# Final.net
KiCad netlist of a schematic drawn in EAGLE
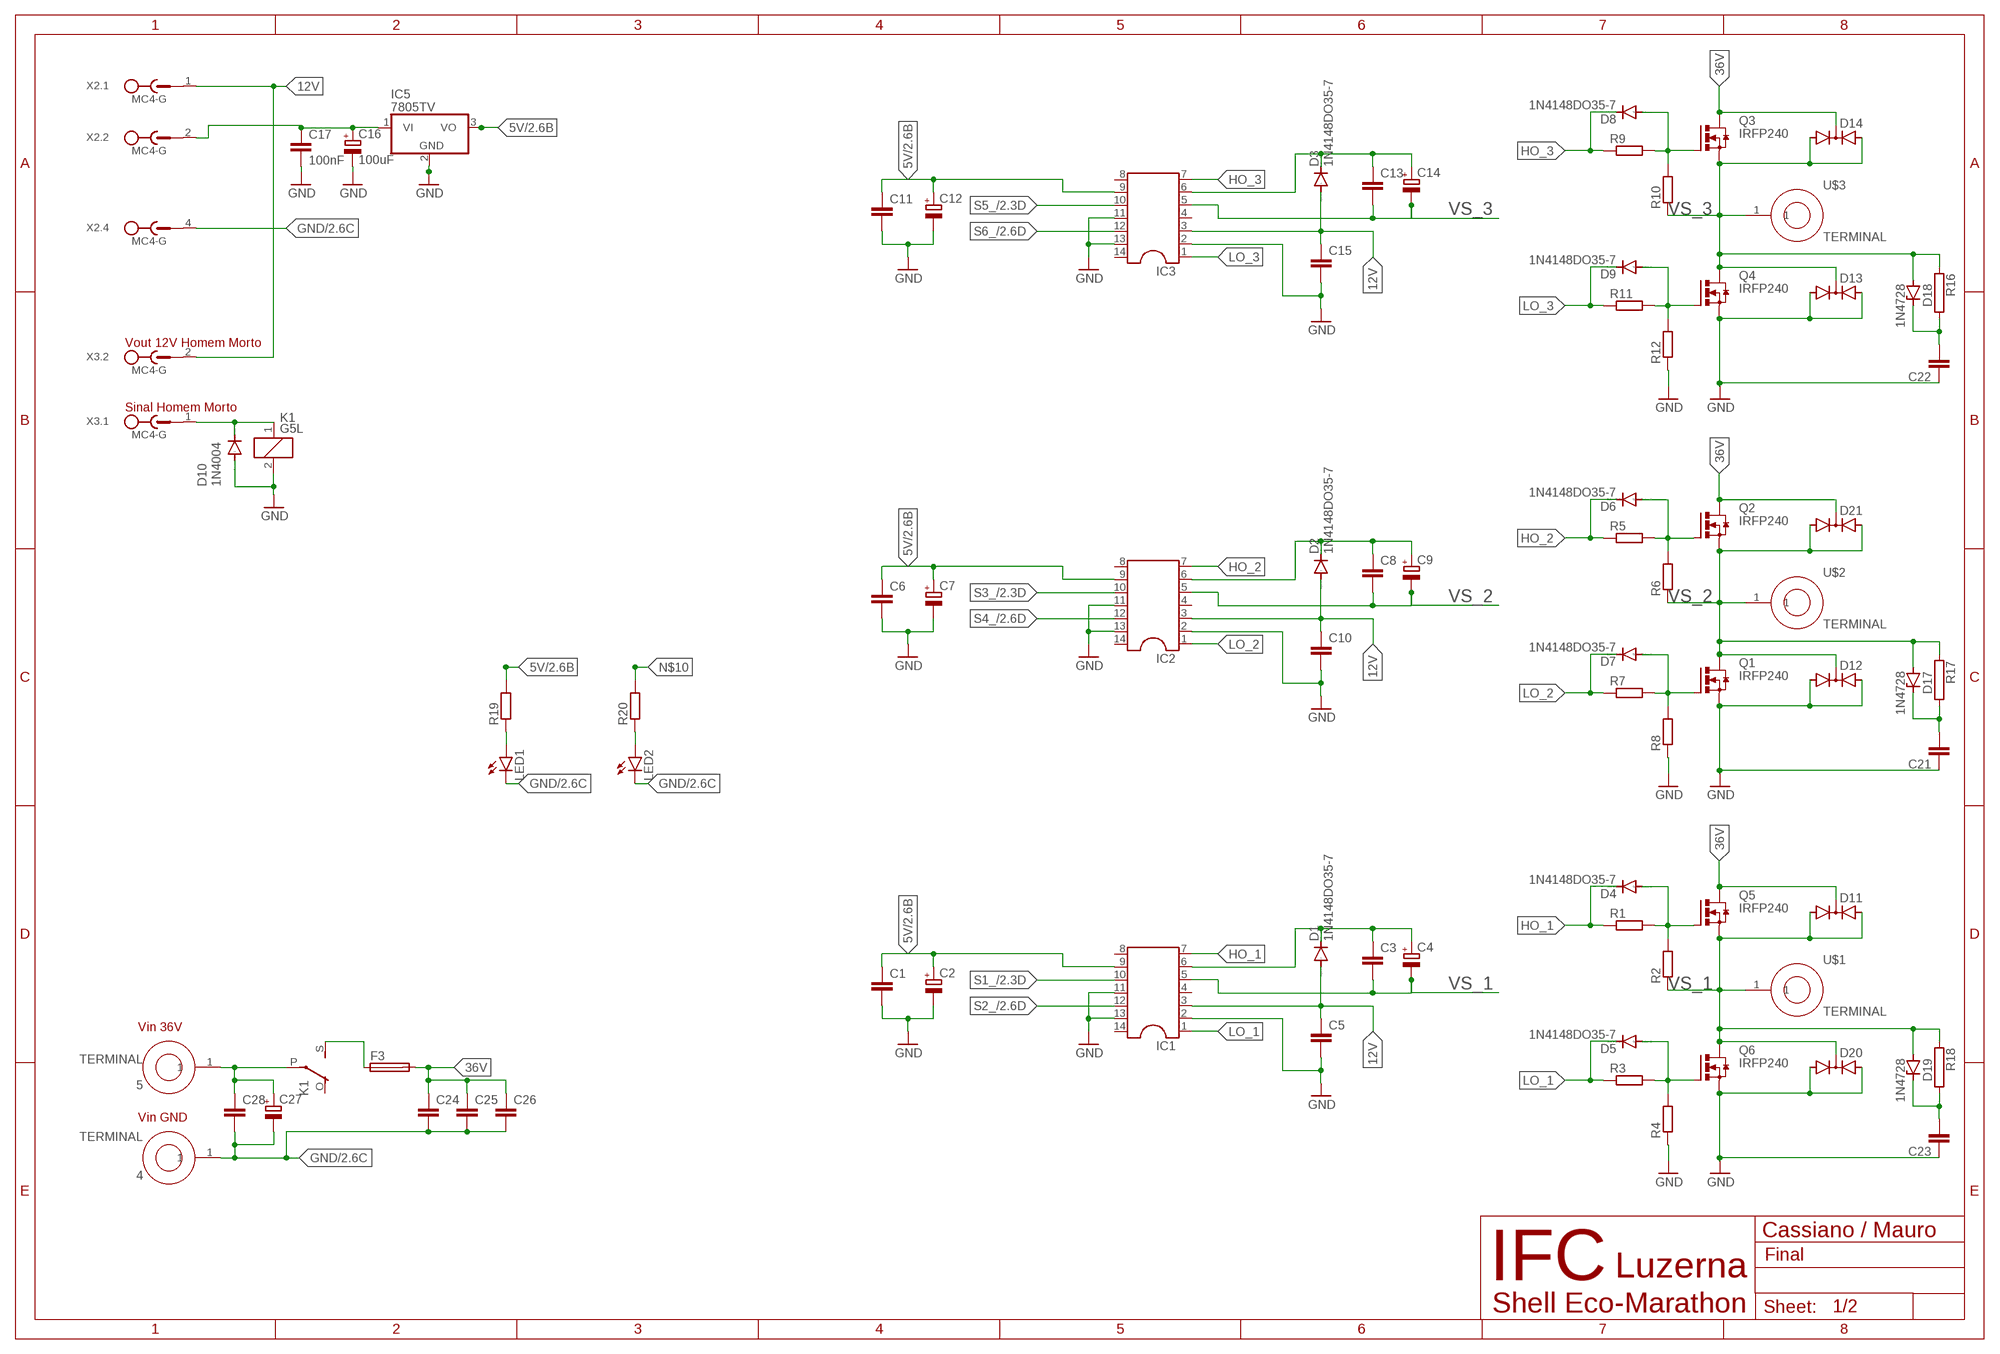
[diagram p0: schematic, sheet 1]
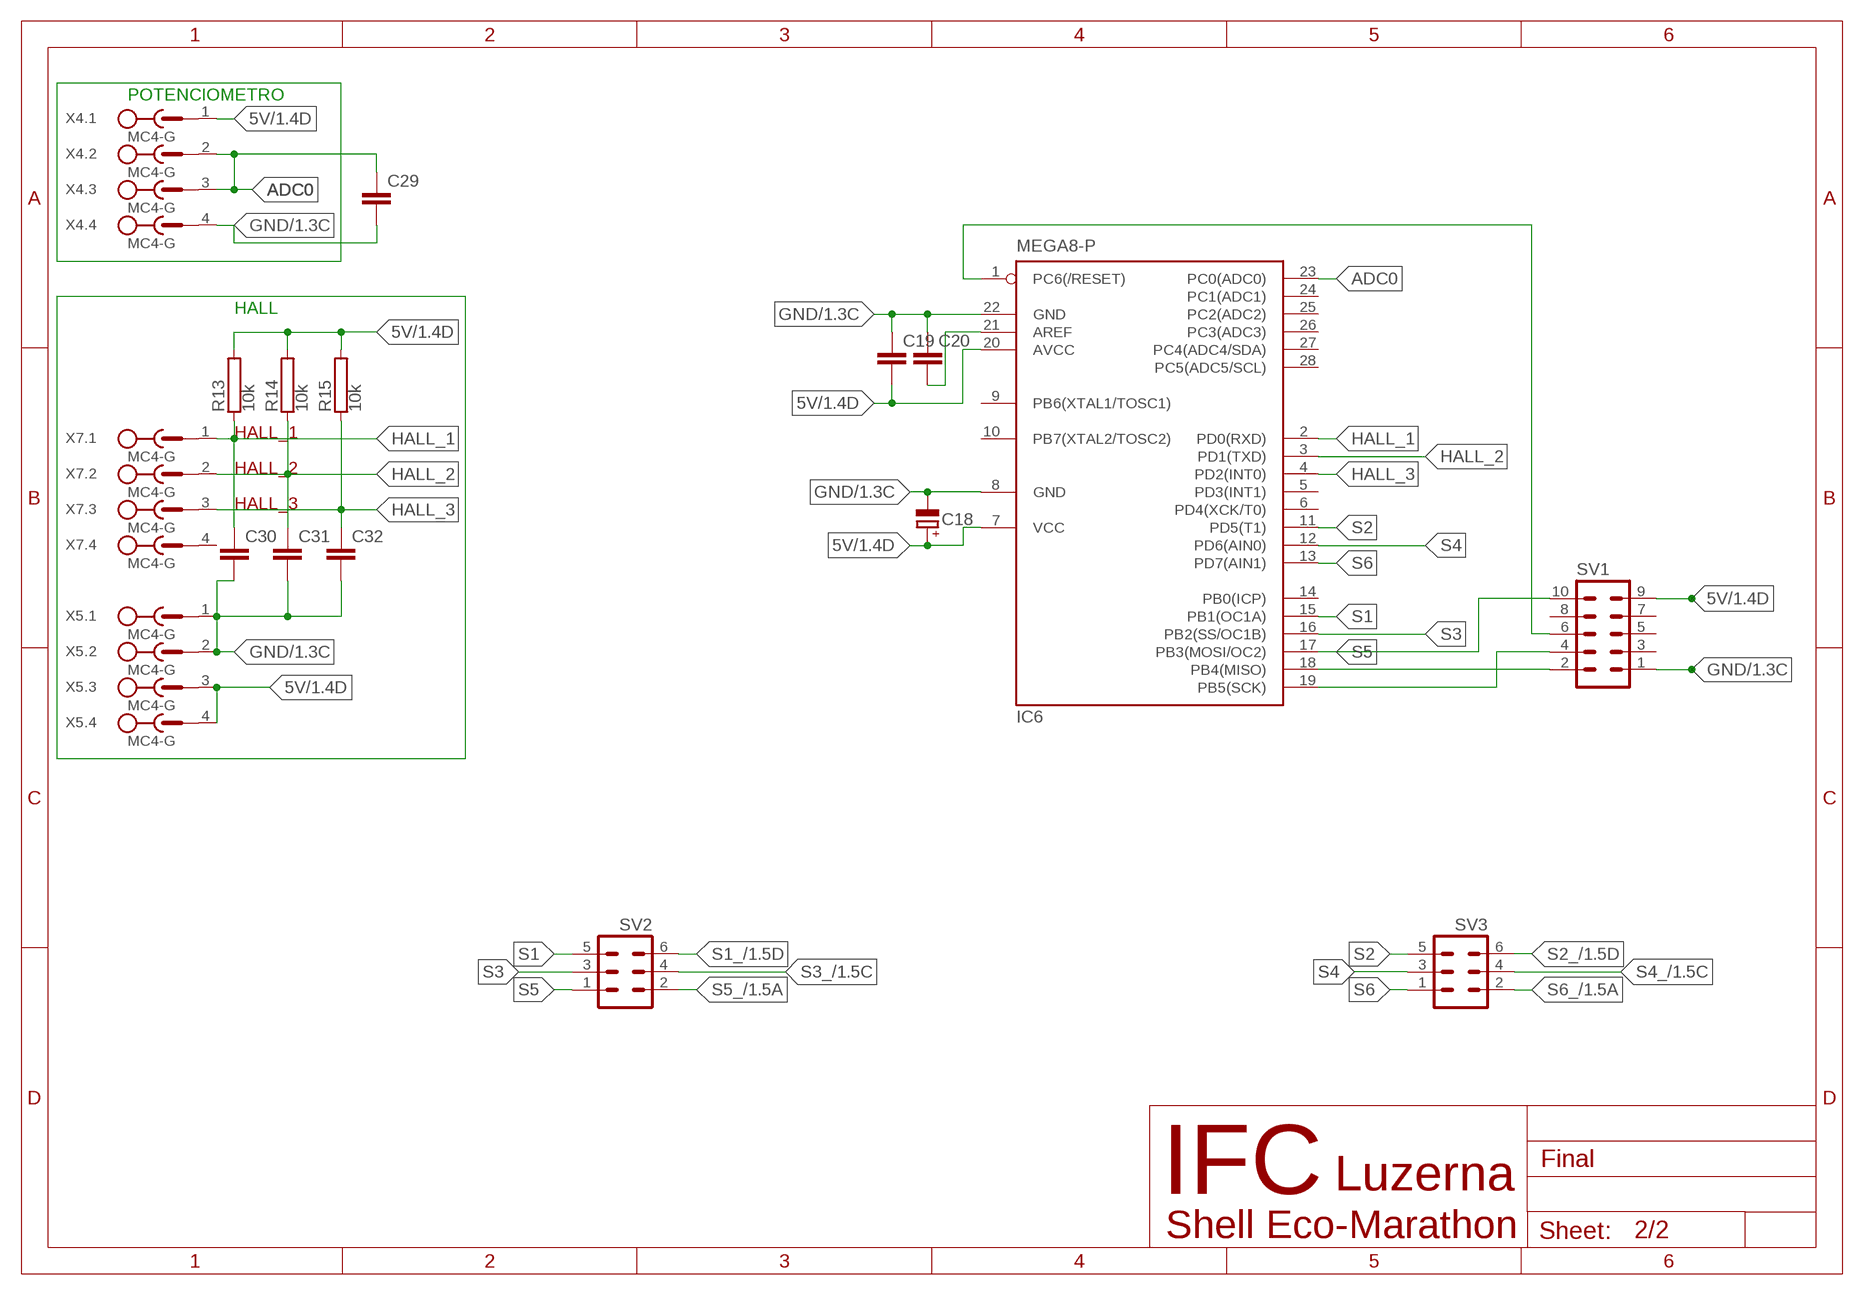
[diagram p1: schematic, sheet 2]

(export (version "E")
  (design (tool "Eeschema 10.0.6"))
  (components
    (comp (ref "4")
      (value "TERMINAL")
      (footprint "eagle-import:TERMINAL")
      (libsource (lib "eagle-import") (part "TERMINAL"))
    )
    (comp (ref "5")
      (value "TERMINAL")
      (footprint "eagle-import:TERMINAL")
      (libsource (lib "eagle-import") (part "TERMINAL"))
    )
    (comp (ref "C1")
      (value "C-EU050-045X075")
      (footprint "eagle-import:C050-045X075")
      (libsource (lib "eagle-import") (part "C-EU050-045X075"))
    )
    (comp (ref "C2")
      (value "CPOL-EUE2.5-7")
      (footprint "eagle-import:E2,5-7")
      (libsource (lib "eagle-import") (part "CPOL-EUE2.5-7"))
    )
    (comp (ref "C3")
      (value "C-EU050-025X075")
      (footprint "eagle-import:C050-025X075")
      (libsource (lib "eagle-import") (part "C-EU050-025X075"))
    )
    (comp (ref "C4")
      (value "CPOL-EUE2.5-7")
      (footprint "eagle-import:E2,5-7")
      (libsource (lib "eagle-import") (part "CPOL-EUE2.5-7"))
    )
    (comp (ref "C5")
      (value "C-EU050-025X075")
      (footprint "eagle-import:C050-025X075")
      (libsource (lib "eagle-import") (part "C-EU050-025X075"))
    )
    (comp (ref "C6")
      (value "C-EU050-045X075")
      (footprint "eagle-import:C050-045X075")
      (libsource (lib "eagle-import") (part "C-EU050-045X075"))
    )
    (comp (ref "C7")
      (value "CPOL-EUE2.5-7")
      (footprint "eagle-import:E2,5-7")
      (libsource (lib "eagle-import") (part "CPOL-EUE2.5-7"))
    )
    (comp (ref "C8")
      (value "C-EU050-025X075")
      (footprint "eagle-import:C050-025X075")
      (libsource (lib "eagle-import") (part "C-EU050-025X075"))
    )
    (comp (ref "C9")
      (value "CPOL-EUE2.5-7")
      (footprint "eagle-import:E2,5-7")
      (libsource (lib "eagle-import") (part "CPOL-EUE2.5-7"))
    )
    (comp (ref "C10")
      (value "C-EU050-025X075")
      (footprint "eagle-import:C050-025X075")
      (libsource (lib "eagle-import") (part "C-EU050-025X075"))
    )
    (comp (ref "C11")
      (value "C-EU050-045X075")
      (footprint "eagle-import:C050-045X075")
      (libsource (lib "eagle-import") (part "C-EU050-045X075"))
    )
    (comp (ref "C12")
      (value "CPOL-EUE2.5-7")
      (footprint "eagle-import:E2,5-7")
      (libsource (lib "eagle-import") (part "CPOL-EUE2.5-7"))
    )
    (comp (ref "C13")
      (value "C-EU050-025X075")
      (footprint "eagle-import:C050-025X075")
      (libsource (lib "eagle-import") (part "C-EU050-025X075"))
    )
    (comp (ref "C14")
      (value "CPOL-EUE2.5-7")
      (footprint "eagle-import:E2,5-7")
      (libsource (lib "eagle-import") (part "CPOL-EUE2.5-7"))
    )
    (comp (ref "C15")
      (value "C-EU050-025X075")
      (footprint "eagle-import:C050-025X075")
      (libsource (lib "eagle-import") (part "C-EU050-025X075"))
    )
    (comp (ref "C16")
      (value "100uF")
      (footprint "eagle-import:E2,5-7")
      (libsource (lib "eagle-import") (part "CPOL-EUE2.5-7"))
    )
    (comp (ref "C17")
      (value "100nF")
      (footprint "eagle-import:C050-045X075")
      (libsource (lib "eagle-import") (part "C-EU050-045X075"))
    )
    (comp (ref "C21")
      (value "C-EU150-054X183")
      (footprint "eagle-import:C150-054X183")
      (libsource (lib "eagle-import") (part "C-EU150-054X183"))
    )
    (comp (ref "C22")
      (value "C-EU150-054X183")
      (footprint "eagle-import:C150-054X183")
      (libsource (lib "eagle-import") (part "C-EU150-054X183"))
    )
    (comp (ref "C23")
      (value "C-EU150-054X183")
      (footprint "eagle-import:C150-054X183")
      (libsource (lib "eagle-import") (part "C-EU150-054X183"))
    )
    (comp (ref "C24")
      (value "C-EU275-093X316")
      (footprint "eagle-import:C275-093X316")
      (libsource (lib "eagle-import") (part "C-EU275-093X316"))
    )
    (comp (ref "C25")
      (value "C-EU275-093X316")
      (footprint "eagle-import:C275-093X316")
      (libsource (lib "eagle-import") (part "C-EU275-093X316"))
    )
    (comp (ref "C26")
      (value "C-EU275-093X316")
      (footprint "eagle-import:C275-093X316")
      (libsource (lib "eagle-import") (part "C-EU275-093X316"))
    )
    (comp (ref "C27")
      (value "CPOL-EUE10-22.5")
      (footprint "eagle-import:EB22,5D")
      (libsource (lib "eagle-import") (part "CPOL-EUE10-22.5"))
    )
    (comp (ref "C28")
      (value "C-EU275-093X316")
      (footprint "eagle-import:C275-093X316")
      (libsource (lib "eagle-import") (part "C-EU275-093X316"))
    )
    (comp (ref "D1")
      (value "1N4148DO35-7")
      (footprint "eagle-import:DO35-7")
      (libsource (lib "eagle-import") (part "1N4148DO35-7"))
    )
    (comp (ref "D2")
      (value "1N4148DO35-7")
      (footprint "eagle-import:DO35-7")
      (libsource (lib "eagle-import") (part "1N4148DO35-7"))
    )
    (comp (ref "D3")
      (value "1N4148DO35-7")
      (footprint "eagle-import:DO35-7")
      (libsource (lib "eagle-import") (part "1N4148DO35-7"))
    )
    (comp (ref "D4")
      (value "1N4148DO35-7")
      (footprint "eagle-import:DO35-7")
      (libsource (lib "eagle-import") (part "1N4148DO35-7"))
    )
    (comp (ref "D5")
      (value "1N4148DO35-7")
      (footprint "eagle-import:DO35-7")
      (libsource (lib "eagle-import") (part "1N4148DO35-7"))
    )
    (comp (ref "D6")
      (value "1N4148DO35-7")
      (footprint "eagle-import:DO35-7")
      (libsource (lib "eagle-import") (part "1N4148DO35-7"))
    )
    (comp (ref "D7")
      (value "1N4148DO35-7")
      (footprint "eagle-import:DO35-7")
      (libsource (lib "eagle-import") (part "1N4148DO35-7"))
    )
    (comp (ref "D8")
      (value "1N4148DO35-7")
      (footprint "eagle-import:DO35-7")
      (libsource (lib "eagle-import") (part "1N4148DO35-7"))
    )
    (comp (ref "D9")
      (value "1N4148DO35-7")
      (footprint "eagle-import:DO35-7")
      (libsource (lib "eagle-import") (part "1N4148DO35-7"))
    )
    (comp (ref "D10")
      (value "1N4004")
      (footprint "eagle-import:DO41-10")
      (libsource (lib "eagle-import") (part "1N4004"))
    )
    (comp (ref "D11")
      (value "DIODE-2AC|CATO220V")
      (footprint "eagle-import:TO220ABS")
      (libsource (lib "eagle-import") (part "DIODE-2AC|CATO220V"))
    )
    (comp (ref "D12")
      (value "DIODE-2AC|CATO220V")
      (footprint "eagle-import:TO220ABS")
      (libsource (lib "eagle-import") (part "DIODE-2AC|CATO220V"))
    )
    (comp (ref "D13")
      (value "DIODE-2AC|CATO220V")
      (footprint "eagle-import:TO220ABS")
      (libsource (lib "eagle-import") (part "DIODE-2AC|CATO220V"))
    )
    (comp (ref "D14")
      (value "DIODE-2AC|CATO220V")
      (footprint "eagle-import:TO220ABS")
      (libsource (lib "eagle-import") (part "DIODE-2AC|CATO220V"))
    )
    (comp (ref "D17")
      (value "1N4728")
      (footprint "eagle-import:DO41Z10")
      (libsource (lib "eagle-import") (part "1N4728"))
    )
    (comp (ref "D18")
      (value "1N4728")
      (footprint "eagle-import:DO41Z10")
      (libsource (lib "eagle-import") (part "1N4728"))
    )
    (comp (ref "D19")
      (value "1N4728")
      (footprint "eagle-import:DO41Z10")
      (libsource (lib "eagle-import") (part "1N4728"))
    )
    (comp (ref "D20")
      (value "DIODE-2AC|CATO220V")
      (footprint "eagle-import:TO220ABS")
      (libsource (lib "eagle-import") (part "DIODE-2AC|CATO220V"))
    )
    (comp (ref "D21")
      (value "DIODE-2AC|CATO220V")
      (footprint "eagle-import:TO220ABS")
      (libsource (lib "eagle-import") (part "DIODE-2AC|CATO220V"))
    )
    (comp (ref "F3")
      (value "SH22,5A")
      (footprint "eagle-import:SH22,5A")
      (fields (field (name "MPN") "0031.7701.11"))
      (libsource (lib "eagle-import") (part "SH22,5A"))
    )
    (comp (ref "IC1")
      (value "DIL14")
      (footprint "eagle-import:DIL14")
      (libsource (lib "eagle-import") (part "DIL14"))
    )
    (comp (ref "IC2")
      (value "DIL14")
      (footprint "eagle-import:DIL14")
      (libsource (lib "eagle-import") (part "DIL14"))
    )
    (comp (ref "IC3")
      (value "DIL14")
      (footprint "eagle-import:DIL14")
      (libsource (lib "eagle-import") (part "DIL14"))
    )
    (comp (ref "IC5")
      (value "7805TV")
      (footprint "eagle-import:TO220V")
      (libsource (lib "eagle-import") (part "78TV05"))
    )
    (comp (ref "K1")
      (value "G5L")
      (footprint "eagle-import:G5LE")
      (libsource (lib "eagle-import") (part "G5L"))
    )
    (comp (ref "LED1")
      (value "LED5MM")
      (footprint "eagle-import:LED5MM")
      (libsource (lib "eagle-import") (part "LED5MM"))
    )
    (comp (ref "LED2")
      (value "LED5MM")
      (footprint "eagle-import:LED5MM")
      (libsource (lib "eagle-import") (part "LED5MM"))
    )
    (comp (ref "Q1")
      (value "IRFP240")
      (footprint "eagle-import:TO247BV")
      (libsource (lib "eagle-import") (part "IRFP240"))
    )
    (comp (ref "Q2")
      (value "IRFP240")
      (footprint "eagle-import:TO247BV")
      (libsource (lib "eagle-import") (part "IRFP240"))
    )
    (comp (ref "Q3")
      (value "IRFP240")
      (footprint "eagle-import:TO247BV")
      (libsource (lib "eagle-import") (part "IRFP240"))
    )
    (comp (ref "Q4")
      (value "IRFP240")
      (footprint "eagle-import:TO247BV")
      (libsource (lib "eagle-import") (part "IRFP240"))
    )
    (comp (ref "Q5")
      (value "IRFP240")
      (footprint "eagle-import:TO247BV")
      (libsource (lib "eagle-import") (part "IRFP240"))
    )
    (comp (ref "Q6")
      (value "IRFP240")
      (footprint "eagle-import:TO247BV")
      (libsource (lib "eagle-import") (part "IRFP240"))
    )
    (comp (ref "R1")
      (value "R-EU_0204/7")
      (footprint "eagle-import:0204_7")
      (libsource (lib "eagle-import") (part "R-EU_0204/7"))
    )
    (comp (ref "R2")
      (value "R-EU_0204/7")
      (footprint "eagle-import:0204_7")
      (libsource (lib "eagle-import") (part "R-EU_0204/7"))
    )
    (comp (ref "R3")
      (value "R-EU_0204/7")
      (footprint "eagle-import:0204_7")
      (libsource (lib "eagle-import") (part "R-EU_0204/7"))
    )
    (comp (ref "R4")
      (value "R-EU_0204/7")
      (footprint "eagle-import:0204_7")
      (libsource (lib "eagle-import") (part "R-EU_0204/7"))
    )
    (comp (ref "R5")
      (value "R-EU_0204/7")
      (footprint "eagle-import:0204_7")
      (libsource (lib "eagle-import") (part "R-EU_0204/7"))
    )
    (comp (ref "R6")
      (value "R-EU_0204/7")
      (footprint "eagle-import:0204_7")
      (libsource (lib "eagle-import") (part "R-EU_0204/7"))
    )
    (comp (ref "R7")
      (value "R-EU_0204/7")
      (footprint "eagle-import:0204_7")
      (libsource (lib "eagle-import") (part "R-EU_0204/7"))
    )
    (comp (ref "R8")
      (value "R-EU_0204/7")
      (footprint "eagle-import:0204_7")
      (libsource (lib "eagle-import") (part "R-EU_0204/7"))
    )
    (comp (ref "R9")
      (value "R-EU_0204/7")
      (footprint "eagle-import:0204_7")
      (libsource (lib "eagle-import") (part "R-EU_0204/7"))
    )
    (comp (ref "R10")
      (value "R-EU_0204/7")
      (footprint "eagle-import:0204_7")
      (libsource (lib "eagle-import") (part "R-EU_0204/7"))
    )
    (comp (ref "R11")
      (value "R-EU_0204/7")
      (footprint "eagle-import:0204_7")
      (libsource (lib "eagle-import") (part "R-EU_0204/7"))
    )
    (comp (ref "R12")
      (value "R-EU_0204/7")
      (footprint "eagle-import:0204_7")
      (libsource (lib "eagle-import") (part "R-EU_0204/7"))
    )
    (comp (ref "R16")
      (value "RCA4150")
      (footprint "eagle-import:CA4150")
      (libsource (lib "eagle-import") (part "RCA4150"))
    )
    (comp (ref "R17")
      (value "RCA4150")
      (footprint "eagle-import:CA4150")
      (libsource (lib "eagle-import") (part "RCA4150"))
    )
    (comp (ref "R18")
      (value "RCA4150")
      (footprint "eagle-import:CA4150")
      (libsource (lib "eagle-import") (part "RCA4150"))
    )
    (comp (ref "R19")
      (value "R-EU_0204/7")
      (footprint "eagle-import:0204_7")
      (libsource (lib "eagle-import") (part "R-EU_0204/7"))
    )
    (comp (ref "R20")
      (value "R-EU_0204/7")
      (footprint "eagle-import:0204_7")
      (libsource (lib "eagle-import") (part "R-EU_0204/7"))
    )
    (comp (ref "U$1")
      (value "TERMINAL")
      (footprint "eagle-import:TERMINAL")
      (libsource (lib "eagle-import") (part "TERMINAL"))
    )
    (comp (ref "U$2")
      (value "TERMINAL")
      (footprint "eagle-import:TERMINAL")
      (libsource (lib "eagle-import") (part "TERMINAL"))
    )
    (comp (ref "U$3")
      (value "TERMINAL")
      (footprint "eagle-import:TERMINAL")
      (libsource (lib "eagle-import") (part "TERMINAL"))
    )
    (comp (ref "X2")
      (value "MC4-G")
      (footprint "eagle-import:MC4-G")
      (libsource (lib "eagle-import") (part "MC4-G"))
    )
    (comp (ref "X3")
      (value "MC4-G")
      (footprint "eagle-import:MC4-G")
      (libsource (lib "eagle-import") (part "MC4-G"))
    )
    (comp (ref "C18")
      (value "CPOL-EUE3.5-10")
      (footprint "eagle-import:E3,5-10")
      (libsource (lib "eagle-import") (part "CPOL-EUE3.5-10"))
    )
    (comp (ref "C19")
      (value "C-EU075-032X103")
      (footprint "eagle-import:C075-032X103")
      (libsource (lib "eagle-import") (part "C-EU075-032X103"))
    )
    (comp (ref "C20")
      (value "C-EU075-032X103")
      (footprint "eagle-import:C075-032X103")
      (libsource (lib "eagle-import") (part "C-EU075-032X103"))
    )
    (comp (ref "C29")
      (value "C-EU075-032X103")
      (footprint "eagle-import:C075-032X103")
      (libsource (lib "eagle-import") (part "C-EU075-032X103"))
    )
    (comp (ref "C30")
      (value "C-EU075-032X103")
      (footprint "eagle-import:C075-032X103")
      (libsource (lib "eagle-import") (part "C-EU075-032X103"))
    )
    (comp (ref "C31")
      (value "C-EU075-032X103")
      (footprint "eagle-import:C075-032X103")
      (libsource (lib "eagle-import") (part "C-EU075-032X103"))
    )
    (comp (ref "C32")
      (value "C-EU075-032X103")
      (footprint "eagle-import:C075-032X103")
      (libsource (lib "eagle-import") (part "C-EU075-032X103"))
    )
    (comp (ref "IC6")
      (value "MEGA8-P")
      (footprint "eagle-import:DIL28-3")
      (libsource (lib "eagle-import") (part "MEGA8-P"))
    )
    (comp (ref "R13")
      (value "10k")
      (footprint "eagle-import:RS1_4")
      (fields (field (name "MF") "OHMITE") (field (name "MPN") "RRS1K0"))
      (libsource (lib "eagle-import") (part "RRS1/4"))
    )
    (comp (ref "R14")
      (value "10k")
      (footprint "eagle-import:RS1_4")
      (fields (field (name "MF") "OHMITE") (field (name "MPN") "RRS1K0"))
      (libsource (lib "eagle-import") (part "RRS1/4"))
    )
    (comp (ref "R15")
      (value "10k")
      (footprint "eagle-import:RS1_4")
      (fields (field (name "MF") "OHMITE") (field (name "MPN") "RRS1K0"))
      (libsource (lib "eagle-import") (part "RRS1/4"))
    )
    (comp (ref "SV1")
      (value "MA05-2")
      (footprint "eagle-import:MA05-2")
      (libsource (lib "eagle-import") (part "MA05-2"))
    )
    (comp (ref "SV2")
      (value "MA03-2")
      (footprint "eagle-import:MA03-2")
      (libsource (lib "eagle-import") (part "MA03-2"))
    )
    (comp (ref "SV3")
      (value "MA03-2")
      (footprint "eagle-import:MA03-2")
      (libsource (lib "eagle-import") (part "MA03-2"))
    )
    (comp (ref "X4")
      (value "MC4-G")
      (footprint "eagle-import:MC4-G")
      (libsource (lib "eagle-import") (part "MC4-G"))
    )
    (comp (ref "X5")
      (value "MC4-G")
      (footprint "eagle-import:MC4-G")
      (libsource (lib "eagle-import") (part "MC4-G"))
    )
    (comp (ref "X7")
      (value "MC4-G")
      (footprint "eagle-import:MC4-G")
      (libsource (lib "eagle-import") (part "MC4-G"))
    )
  )
  (nets
    (net (code "1") (name "5V") (class "Default")
      (node (ref "C1") (pin "1") (pinfunction "1_1") (pintype "passive"))
      (node (ref "C11") (pin "1") (pinfunction "1_1") (pintype "passive"))
      (node (ref "C12") (pin "+") (pinfunction "+_+") (pintype "passive"))
      (node (ref "C18") (pin "+") (pinfunction "+_+") (pintype "passive"))
      (node (ref "C19") (pin "2") (pinfunction "2_2") (pintype "passive"))
      (node (ref "C2") (pin "+") (pinfunction "+_+") (pintype "passive"))
      (node (ref "C6") (pin "1") (pinfunction "1_1") (pintype "passive"))
      (node (ref "C7") (pin "+") (pinfunction "+_+") (pintype "passive"))
      (node (ref "IC1") (pin "9") (pinfunction "9_9") (pintype "passive"))
      (node (ref "IC2") (pin "9") (pinfunction "9_9") (pintype "passive"))
      (node (ref "IC3") (pin "9") (pinfunction "9_9") (pintype "passive"))
      (node (ref "IC5") (pin "3") (pinfunction "VO_3") (pintype "passive"))
      (node (ref "IC6") (pin "20") (pinfunction "AVCC_20") (pintype "power_in"))
      (node (ref "IC6") (pin "7") (pinfunction "VCC_7") (pintype "power_in"))
      (node (ref "R13") (pin "2") (pinfunction "2_2") (pintype "passive"))
      (node (ref "R14") (pin "2") (pinfunction "2_2") (pintype "passive"))
      (node (ref "R15") (pin "2") (pinfunction "2_2") (pintype "passive"))
      (node (ref "R19") (pin "2") (pinfunction "2_2") (pintype "passive"))
      (node (ref "SV1") (pin "9") (pinfunction "9_9") (pintype "passive"))
      (node (ref "X4") (pin "1") (pinfunction "SK_1") (pintype "passive"))
      (node (ref "X5") (pin "3") (pinfunction "SK_3") (pintype "passive"))
      (node (ref "X5") (pin "4") (pinfunction "SK_4") (pintype "passive"))
    )
    (net (code "2") (name "12V") (class "Default")
      (node (ref "C10") (pin "1") (pinfunction "1_1") (pintype "passive"))
      (node (ref "C15") (pin "1") (pinfunction "1_1") (pintype "passive"))
      (node (ref "C5") (pin "1") (pinfunction "1_1") (pintype "passive"))
      (node (ref "D1") (pin "A") (pinfunction "A_A") (pintype "passive"))
      (node (ref "D2") (pin "A") (pinfunction "A_A") (pintype "passive"))
      (node (ref "D3") (pin "A") (pinfunction "A_A") (pintype "passive"))
      (node (ref "IC1") (pin "3") (pinfunction "3_3") (pintype "passive"))
      (node (ref "IC2") (pin "3") (pinfunction "3_3") (pintype "passive"))
      (node (ref "IC3") (pin "3") (pinfunction "3_3") (pintype "passive"))
      (node (ref "X2") (pin "1") (pinfunction "SK_1") (pintype "passive"))
      (node (ref "X3") (pin "2") (pinfunction "SK_2") (pintype "passive"))
    )
    (net (code "3") (name "36V") (class "Default")
      (node (ref "C24") (pin "1") (pinfunction "1_1") (pintype "passive"))
      (node (ref "C25") (pin "1") (pinfunction "1_1") (pintype "passive"))
      (node (ref "C26") (pin "1") (pinfunction "1_1") (pintype "passive"))
      (node (ref "D11") (pin "C") (pinfunction "C_C") (pintype "passive"))
      (node (ref "D14") (pin "C") (pinfunction "C_C") (pintype "passive"))
      (node (ref "D21") (pin "C") (pinfunction "C_C") (pintype "passive"))
      (node (ref "F3") (pin "2") (pinfunction "2_2") (pintype "passive"))
      (node (ref "Q2") (pin "D") (pinfunction "D_D") (pintype "passive"))
      (node (ref "Q3") (pin "D") (pinfunction "D_D") (pintype "passive"))
      (node (ref "Q5") (pin "D") (pinfunction "D_D") (pintype "passive"))
    )
    (net (code "4") (name "ADC0") (class "Default")
      (node (ref "C29") (pin "1") (pinfunction "1_1") (pintype "passive"))
      (node (ref "IC6") (pin "23") (pinfunction "PC0(ADC0)_23") (pintype "bidirectional"))
      (node (ref "X4") (pin "2") (pinfunction "SK_2") (pintype "passive"))
      (node (ref "X4") (pin "3") (pinfunction "SK_3") (pintype "passive"))
    )
    (net (code "5") (name "GND") (class "Default")
      (node (ref "4") (pin "1") (pinfunction "1_1") (pintype "bidirectional"))
      (node (ref "C1") (pin "2") (pinfunction "2_2") (pintype "passive"))
      (node (ref "C10") (pin "2") (pinfunction "2_2") (pintype "passive"))
      (node (ref "C11") (pin "2") (pinfunction "2_2") (pintype "passive"))
      (node (ref "C12") (pin "-") (pinfunction "-_-") (pintype "passive"))
      (node (ref "C15") (pin "2") (pinfunction "2_2") (pintype "passive"))
      (node (ref "C16") (pin "-") (pinfunction "-_-") (pintype "passive"))
      (node (ref "C17") (pin "2") (pinfunction "2_2") (pintype "passive"))
      (node (ref "C18") (pin "-") (pinfunction "-_-") (pintype "passive"))
      (node (ref "C19") (pin "1") (pinfunction "1_1") (pintype "passive"))
      (node (ref "C2") (pin "-") (pinfunction "-_-") (pintype "passive"))
      (node (ref "C20") (pin "1") (pinfunction "1_1") (pintype "passive"))
      (node (ref "C21") (pin "1") (pinfunction "1_1") (pintype "passive"))
      (node (ref "C22") (pin "1") (pinfunction "1_1") (pintype "passive"))
      (node (ref "C23") (pin "1") (pinfunction "1_1") (pintype "passive"))
      (node (ref "C24") (pin "2") (pinfunction "2_2") (pintype "passive"))
      (node (ref "C25") (pin "2") (pinfunction "2_2") (pintype "passive"))
      (node (ref "C26") (pin "2") (pinfunction "2_2") (pintype "passive"))
      (node (ref "C27") (pin "-") (pinfunction "-_-") (pintype "passive"))
      (node (ref "C28") (pin "2") (pinfunction "2_2") (pintype "passive"))
      (node (ref "C29") (pin "2") (pinfunction "2_2") (pintype "passive"))
      (node (ref "C30") (pin "2") (pinfunction "2_2") (pintype "passive"))
      (node (ref "C31") (pin "2") (pinfunction "2_2") (pintype "passive"))
      (node (ref "C32") (pin "2") (pinfunction "2_2") (pintype "passive"))
      (node (ref "C5") (pin "2") (pinfunction "2_2") (pintype "passive"))
      (node (ref "C6") (pin "2") (pinfunction "2_2") (pintype "passive"))
      (node (ref "C7") (pin "-") (pinfunction "-_-") (pintype "passive"))
      (node (ref "D10") (pin "A") (pinfunction "A_A") (pintype "passive"))
      (node (ref "D12") (pin "A1") (pinfunction "A1_A1") (pintype "passive"))
      (node (ref "D12") (pin "A2") (pinfunction "A2_A2") (pintype "passive"))
      (node (ref "D13") (pin "A1") (pinfunction "A1_A1") (pintype "passive"))
      (node (ref "D13") (pin "A2") (pinfunction "A2_A2") (pintype "passive"))
      (node (ref "D20") (pin "A1") (pinfunction "A1_A1") (pintype "passive"))
      (node (ref "D20") (pin "A2") (pinfunction "A2_A2") (pintype "passive"))
      (node (ref "IC1") (pin "11") (pinfunction "11_11") (pintype "passive"))
      (node (ref "IC1") (pin "13") (pinfunction "13_13") (pintype "passive"))
      (node (ref "IC1") (pin "2") (pinfunction "2_2") (pintype "passive"))
      (node (ref "IC2") (pin "11") (pinfunction "11_11") (pintype "passive"))
      (node (ref "IC2") (pin "13") (pinfunction "13_13") (pintype "passive"))
      (node (ref "IC2") (pin "2") (pinfunction "2_2") (pintype "passive"))
      (node (ref "IC3") (pin "11") (pinfunction "11_11") (pintype "passive"))
      (node (ref "IC3") (pin "13") (pinfunction "13_13") (pintype "passive"))
      (node (ref "IC3") (pin "2") (pinfunction "2_2") (pintype "passive"))
      (node (ref "IC5") (pin "2") (pinfunction "GND_2") (pintype "passive"))
      (node (ref "IC6") (pin "22") (pinfunction "GND_22") (pintype "power_in"))
      (node (ref "IC6") (pin "8") (pinfunction "GND_8") (pintype "power_in"))
      (node (ref "K1") (pin "2") (pinfunction "2_2") (pintype "passive"))
      (node (ref "LED1") (pin "K") (pinfunction "C_K") (pintype "passive"))
      (node (ref "LED2") (pin "K") (pinfunction "C_K") (pintype "passive"))
      (node (ref "Q1") (pin "S") (pinfunction "S_S") (pintype "passive"))
      (node (ref "Q4") (pin "S") (pinfunction "S_S") (pintype "passive"))
      (node (ref "Q6") (pin "S") (pinfunction "S_S") (pintype "passive"))
      (node (ref "R12") (pin "1") (pinfunction "1_1") (pintype "passive"))
      (node (ref "R4") (pin "1") (pinfunction "1_1") (pintype "passive"))
      (node (ref "R8") (pin "1") (pinfunction "1_1") (pintype "passive"))
      (node (ref "SV1") (pin "1") (pinfunction "1_1") (pintype "passive"))
      (node (ref "X2") (pin "4") (pinfunction "SK_4") (pintype "passive"))
      (node (ref "X4") (pin "4") (pinfunction "SK_4") (pintype "passive"))
      (node (ref "X5") (pin "1") (pinfunction "SK_1") (pintype "passive"))
      (node (ref "X5") (pin "2") (pinfunction "SK_2") (pintype "passive"))
    )
    (net (code "6") (name "HALL_1") (class "Default")
      (node (ref "C30") (pin "1") (pinfunction "1_1") (pintype "passive"))
      (node (ref "IC6") (pin "2") (pinfunction "PD0(RXD)_2") (pintype "bidirectional"))
      (node (ref "R13") (pin "1") (pinfunction "1_1") (pintype "passive"))
      (node (ref "X7") (pin "1") (pinfunction "SK_1") (pintype "passive"))
    )
    (net (code "7") (name "HALL_2") (class "Default")
      (node (ref "C31") (pin "1") (pinfunction "1_1") (pintype "passive"))
      (node (ref "IC6") (pin "3") (pinfunction "PD1(TXD)_3") (pintype "bidirectional"))
      (node (ref "R14") (pin "1") (pinfunction "1_1") (pintype "passive"))
      (node (ref "X7") (pin "2") (pinfunction "SK_2") (pintype "passive"))
    )
    (net (code "8") (name "HALL_3") (class "Default")
      (node (ref "C32") (pin "1") (pinfunction "1_1") (pintype "passive"))
      (node (ref "IC6") (pin "4") (pinfunction "PD2(INT0)_4") (pintype "bidirectional"))
      (node (ref "R15") (pin "1") (pinfunction "1_1") (pintype "passive"))
      (node (ref "X7") (pin "3") (pinfunction "SK_3") (pintype "passive"))
    )
    (net (code "9") (name "HO_1") (class "Default")
      (node (ref "D4") (pin "C") (pinfunction "C_C") (pintype "passive"))
      (node (ref "IC1") (pin "7") (pinfunction "7_7") (pintype "passive"))
      (node (ref "R1") (pin "1") (pinfunction "1_1") (pintype "passive"))
    )
    (net (code "10") (name "HO_2") (class "Default")
      (node (ref "D6") (pin "C") (pinfunction "C_C") (pintype "passive"))
      (node (ref "IC2") (pin "7") (pinfunction "7_7") (pintype "passive"))
      (node (ref "R5") (pin "1") (pinfunction "1_1") (pintype "passive"))
    )
    (net (code "11") (name "HO_3") (class "Default")
      (node (ref "D8") (pin "C") (pinfunction "C_C") (pintype "passive"))
      (node (ref "IC3") (pin "7") (pinfunction "7_7") (pintype "passive"))
      (node (ref "R9") (pin "1") (pinfunction "1_1") (pintype "passive"))
    )
    (net (code "12") (name "LO_1") (class "Default")
      (node (ref "D5") (pin "C") (pinfunction "C_C") (pintype "passive"))
      (node (ref "IC1") (pin "1") (pinfunction "1_1") (pintype "passive"))
      (node (ref "R3") (pin "1") (pinfunction "1_1") (pintype "passive"))
    )
    (net (code "13") (name "LO_2") (class "Default")
      (node (ref "D7") (pin "C") (pinfunction "C_C") (pintype "passive"))
      (node (ref "IC2") (pin "1") (pinfunction "1_1") (pintype "passive"))
      (node (ref "R7") (pin "1") (pinfunction "1_1") (pintype "passive"))
    )
    (net (code "14") (name "LO_3") (class "Default")
      (node (ref "D9") (pin "C") (pinfunction "C_C") (pintype "passive"))
      (node (ref "IC3") (pin "1") (pinfunction "1_1") (pintype "passive"))
      (node (ref "R11") (pin "1") (pinfunction "1_1") (pintype "passive"))
    )
    (net (code "15") (name "N$10") (class "Default")
      (node (ref "D10") (pin "C") (pinfunction "C_C") (pintype "passive"))
      (node (ref "K1") (pin "1") (pinfunction "1_1") (pintype "passive"))
      (node (ref "R20") (pin "2") (pinfunction "2_2") (pintype "passive"))
      (node (ref "X3") (pin "1") (pinfunction "SK_1") (pintype "passive"))
    )
    (net (code "16") (name "Net-(5-Pad1)") (class "Default")
      (node (ref "5") (pin "1") (pinfunction "1_1") (pintype "bidirectional"))
      (node (ref "C27") (pin "+") (pinfunction "+_+") (pintype "passive"))
      (node (ref "C28") (pin "1") (pinfunction "1_1") (pintype "passive"))
      (node (ref "K1") (pin "P") (pinfunction "P_P") (pintype "passive"))
    )
    (net (code "17") (name "Net-(C3-Pad1)") (class "Default")
      (node (ref "C3") (pin "1") (pinfunction "1_1") (pintype "passive"))
      (node (ref "C4") (pin "+") (pinfunction "+_+") (pintype "passive"))
      (node (ref "D1") (pin "C") (pinfunction "C_C") (pintype "passive"))
      (node (ref "IC1") (pin "6") (pinfunction "6_6") (pintype "passive"))
    )
    (net (code "18") (name "Net-(C8-Pad1)") (class "Default")
      (node (ref "C8") (pin "1") (pinfunction "1_1") (pintype "passive"))
      (node (ref "C9") (pin "+") (pinfunction "+_+") (pintype "passive"))
      (node (ref "D2") (pin "C") (pinfunction "C_C") (pintype "passive"))
      (node (ref "IC2") (pin "6") (pinfunction "6_6") (pintype "passive"))
    )
    (net (code "19") (name "Net-(C13-Pad1)") (class "Default")
      (node (ref "C13") (pin "1") (pinfunction "1_1") (pintype "passive"))
      (node (ref "C14") (pin "+") (pinfunction "+_+") (pintype "passive"))
      (node (ref "D3") (pin "C") (pinfunction "C_C") (pintype "passive"))
      (node (ref "IC3") (pin "6") (pinfunction "6_6") (pintype "passive"))
    )
    (net (code "20") (name "Net-(C21-Pad2)") (class "Default")
      (node (ref "C21") (pin "2") (pinfunction "2_2") (pintype "passive"))
      (node (ref "D17") (pin "C") (pinfunction "C_C") (pintype "passive"))
      (node (ref "R17") (pin "2") (pinfunction "2_2") (pintype "passive"))
    )
    (net (code "21") (name "Net-(C22-Pad2)") (class "Default")
      (node (ref "C22") (pin "2") (pinfunction "2_2") (pintype "passive"))
      (node (ref "D18") (pin "C") (pinfunction "C_C") (pintype "passive"))
      (node (ref "R16") (pin "2") (pinfunction "2_2") (pintype "passive"))
    )
    (net (code "22") (name "Net-(C23-Pad2)") (class "Default")
      (node (ref "C23") (pin "2") (pinfunction "2_2") (pintype "passive"))
      (node (ref "D19") (pin "C") (pinfunction "C_C") (pintype "passive"))
      (node (ref "R18") (pin "2") (pinfunction "2_2") (pintype "passive"))
    )
    (net (code "23") (name "Net-(D4-PadA)") (class "Default")
      (node (ref "D4") (pin "A") (pinfunction "A_A") (pintype "passive"))
      (node (ref "Q5") (pin "G") (pinfunction "G_G") (pintype "passive"))
      (node (ref "R1") (pin "2") (pinfunction "2_2") (pintype "passive"))
      (node (ref "R2") (pin "2") (pinfunction "2_2") (pintype "passive"))
    )
    (net (code "24") (name "Net-(D5-PadA)") (class "Default")
      (node (ref "D5") (pin "A") (pinfunction "A_A") (pintype "passive"))
      (node (ref "Q6") (pin "G") (pinfunction "G_G") (pintype "passive"))
      (node (ref "R3") (pin "2") (pinfunction "2_2") (pintype "passive"))
      (node (ref "R4") (pin "2") (pinfunction "2_2") (pintype "passive"))
    )
    (net (code "25") (name "Net-(D6-PadA)") (class "Default")
      (node (ref "D6") (pin "A") (pinfunction "A_A") (pintype "passive"))
      (node (ref "Q2") (pin "G") (pinfunction "G_G") (pintype "passive"))
      (node (ref "R5") (pin "2") (pinfunction "2_2") (pintype "passive"))
      (node (ref "R6") (pin "2") (pinfunction "2_2") (pintype "passive"))
    )
    (net (code "26") (name "Net-(D7-PadA)") (class "Default")
      (node (ref "D7") (pin "A") (pinfunction "A_A") (pintype "passive"))
      (node (ref "Q1") (pin "G") (pinfunction "G_G") (pintype "passive"))
      (node (ref "R7") (pin "2") (pinfunction "2_2") (pintype "passive"))
      (node (ref "R8") (pin "2") (pinfunction "2_2") (pintype "passive"))
    )
    (net (code "27") (name "Net-(D8-PadA)") (class "Default")
      (node (ref "D8") (pin "A") (pinfunction "A_A") (pintype "passive"))
      (node (ref "Q3") (pin "G") (pinfunction "G_G") (pintype "passive"))
      (node (ref "R10") (pin "2") (pinfunction "2_2") (pintype "passive"))
      (node (ref "R9") (pin "2") (pinfunction "2_2") (pintype "passive"))
    )
    (net (code "28") (name "Net-(D9-PadA)") (class "Default")
      (node (ref "D9") (pin "A") (pinfunction "A_A") (pintype "passive"))
      (node (ref "Q4") (pin "G") (pinfunction "G_G") (pintype "passive"))
      (node (ref "R11") (pin "2") (pinfunction "2_2") (pintype "passive"))
      (node (ref "R12") (pin "2") (pinfunction "2_2") (pintype "passive"))
    )
    (net (code "29") (name "Net-(F3-Pad1)") (class "Default")
      (node (ref "F3") (pin "1") (pinfunction "1_1") (pintype "passive"))
      (node (ref "K1") (pin "S") (pinfunction "S_S") (pintype "passive"))
    )
    (net (code "30") (name "Net-(IC5-VI)") (class "Default")
      (node (ref "C16") (pin "+") (pinfunction "+_+") (pintype "passive"))
      (node (ref "C17") (pin "1") (pinfunction "1_1") (pintype "passive"))
      (node (ref "IC5") (pin "1") (pinfunction "VI_1") (pintype "input"))
      (node (ref "X2") (pin "2") (pinfunction "SK_2") (pintype "passive"))
    )
    (net (code "31") (name "Net-(IC6-AREF)") (class "Default")
      (node (ref "C20") (pin "2") (pinfunction "2_2") (pintype "passive"))
      (node (ref "IC6") (pin "21") (pinfunction "AREF_21") (pintype "passive"))
    )
    (net (code "32") (name "Net-(IC6-PB4(MISO))") (class "Default")
      (node (ref "IC6") (pin "18") (pinfunction "PB4(MISO)_18") (pintype "bidirectional"))
      (node (ref "SV1") (pin "2") (pinfunction "2_2") (pintype "passive"))
    )
    (net (code "33") (name "Net-(IC6-PB5(SCK))") (class "Default")
      (node (ref "IC6") (pin "19") (pinfunction "PB5(SCK)_19") (pintype "bidirectional"))
      (node (ref "SV1") (pin "4") (pinfunction "4_4") (pintype "passive"))
    )
    (net (code "34") (name "Net-(IC6-PC6({slash}RESET))") (class "Default")
      (node (ref "IC6") (pin "1") (pinfunction "PC6(/RESET)_1") (pintype "bidirectional"))
      (node (ref "SV1") (pin "6") (pinfunction "6_6") (pintype "passive"))
    )
    (net (code "35") (name "Net-(LED1-PadA)") (class "Default")
      (node (ref "LED1") (pin "A") (pinfunction "A_A") (pintype "passive"))
      (node (ref "R19") (pin "1") (pinfunction "1_1") (pintype "passive"))
    )
    (net (code "36") (name "Net-(LED2-PadA)") (class "Default")
      (node (ref "LED2") (pin "A") (pinfunction "A_A") (pintype "passive"))
      (node (ref "R20") (pin "1") (pinfunction "1_1") (pintype "passive"))
    )
    (net (code "37") (name "S1") (class "Default")
      (node (ref "IC6") (pin "15") (pinfunction "PB1(OC1A)_15") (pintype "bidirectional"))
      (node (ref "SV2") (pin "5") (pinfunction "5_5") (pintype "passive"))
    )
    (net (code "38") (name "S1_") (class "Default")
      (node (ref "IC1") (pin "10") (pinfunction "10_10") (pintype "passive"))
      (node (ref "SV2") (pin "6") (pinfunction "6_6") (pintype "passive"))
    )
    (net (code "39") (name "S2") (class "Default")
      (node (ref "IC6") (pin "11") (pinfunction "PD5(T1)_11") (pintype "bidirectional"))
      (node (ref "SV3") (pin "5") (pinfunction "5_5") (pintype "passive"))
    )
    (net (code "40") (name "S2_") (class "Default")
      (node (ref "IC1") (pin "12") (pinfunction "12_12") (pintype "passive"))
      (node (ref "SV3") (pin "6") (pinfunction "6_6") (pintype "passive"))
    )
    (net (code "41") (name "S3") (class "Default")
      (node (ref "IC6") (pin "16") (pinfunction "PB2(SS/OC1B)_16") (pintype "bidirectional"))
      (node (ref "SV2") (pin "3") (pinfunction "3_3") (pintype "passive"))
    )
    (net (code "42") (name "S3_") (class "Default")
      (node (ref "IC2") (pin "10") (pinfunction "10_10") (pintype "passive"))
      (node (ref "SV2") (pin "4") (pinfunction "4_4") (pintype "passive"))
    )
    (net (code "43") (name "S4") (class "Default")
      (node (ref "IC6") (pin "12") (pinfunction "PD6(AIN0)_12") (pintype "bidirectional"))
      (node (ref "SV3") (pin "3") (pinfunction "3_3") (pintype "passive"))
    )
    (net (code "44") (name "S4_") (class "Default")
      (node (ref "IC2") (pin "12") (pinfunction "12_12") (pintype "passive"))
      (node (ref "SV3") (pin "4") (pinfunction "4_4") (pintype "passive"))
    )
    (net (code "45") (name "S5") (class "Default")
      (node (ref "IC6") (pin "17") (pinfunction "PB3(MOSI/OC2)_17") (pintype "bidirectional"))
      (node (ref "SV1") (pin "10") (pinfunction "10_10") (pintype "passive"))
      (node (ref "SV2") (pin "1") (pinfunction "1_1") (pintype "passive"))
    )
    (net (code "46") (name "S5_") (class "Default")
      (node (ref "IC3") (pin "10") (pinfunction "10_10") (pintype "passive"))
      (node (ref "SV2") (pin "2") (pinfunction "2_2") (pintype "passive"))
    )
    (net (code "47") (name "S6") (class "Default")
      (node (ref "IC6") (pin "13") (pinfunction "PD7(AIN1)_13") (pintype "bidirectional"))
      (node (ref "SV3") (pin "1") (pinfunction "1_1") (pintype "passive"))
    )
    (net (code "48") (name "S6_") (class "Default")
      (node (ref "IC3") (pin "12") (pinfunction "12_12") (pintype "passive"))
      (node (ref "SV3") (pin "2") (pinfunction "2_2") (pintype "passive"))
    )
    (net (code "49") (name "VS_1") (class "Default")
      (node (ref "C3") (pin "2") (pinfunction "2_2") (pintype "passive"))
      (node (ref "C4") (pin "-") (pinfunction "-_-") (pintype "passive"))
      (node (ref "D11") (pin "A1") (pinfunction "A1_A1") (pintype "passive"))
      (node (ref "D11") (pin "A2") (pinfunction "A2_A2") (pintype "passive"))
      (node (ref "D19") (pin "A") (pinfunction "A_A") (pintype "passive"))
      (node (ref "D20") (pin "C") (pinfunction "C_C") (pintype "passive"))
      (node (ref "IC1") (pin "5") (pinfunction "5_5") (pintype "passive"))
      (node (ref "Q5") (pin "S") (pinfunction "S_S") (pintype "passive"))
      (node (ref "Q6") (pin "D") (pinfunction "D_D") (pintype "passive"))
      (node (ref "R18") (pin "1") (pinfunction "1_1") (pintype "passive"))
      (node (ref "R2") (pin "1") (pinfunction "1_1") (pintype "passive"))
      (node (ref "U$1") (pin "1") (pinfunction "1_1") (pintype "bidirectional"))
    )
    (net (code "50") (name "VS_2") (class "Default")
      (node (ref "C8") (pin "2") (pinfunction "2_2") (pintype "passive"))
      (node (ref "C9") (pin "-") (pinfunction "-_-") (pintype "passive"))
      (node (ref "D12") (pin "C") (pinfunction "C_C") (pintype "passive"))
      (node (ref "D17") (pin "A") (pinfunction "A_A") (pintype "passive"))
      (node (ref "D21") (pin "A1") (pinfunction "A1_A1") (pintype "passive"))
      (node (ref "D21") (pin "A2") (pinfunction "A2_A2") (pintype "passive"))
      (node (ref "IC2") (pin "5") (pinfunction "5_5") (pintype "passive"))
      (node (ref "Q1") (pin "D") (pinfunction "D_D") (pintype "passive"))
      (node (ref "Q2") (pin "S") (pinfunction "S_S") (pintype "passive"))
      (node (ref "R17") (pin "1") (pinfunction "1_1") (pintype "passive"))
      (node (ref "R6") (pin "1") (pinfunction "1_1") (pintype "passive"))
      (node (ref "U$2") (pin "1") (pinfunction "1_1") (pintype "bidirectional"))
    )
    (net (code "51") (name "VS_3") (class "Default")
      (node (ref "C13") (pin "2") (pinfunction "2_2") (pintype "passive"))
      (node (ref "C14") (pin "-") (pinfunction "-_-") (pintype "passive"))
      (node (ref "D13") (pin "C") (pinfunction "C_C") (pintype "passive"))
      (node (ref "D14") (pin "A1") (pinfunction "A1_A1") (pintype "passive"))
      (node (ref "D14") (pin "A2") (pinfunction "A2_A2") (pintype "passive"))
      (node (ref "D18") (pin "A") (pinfunction "A_A") (pintype "passive"))
      (node (ref "IC3") (pin "5") (pinfunction "5_5") (pintype "passive"))
      (node (ref "Q3") (pin "S") (pinfunction "S_S") (pintype "passive"))
      (node (ref "Q4") (pin "D") (pinfunction "D_D") (pintype "passive"))
      (node (ref "R10") (pin "1") (pinfunction "1_1") (pintype "passive"))
      (node (ref "R16") (pin "1") (pinfunction "1_1") (pintype "passive"))
      (node (ref "U$3") (pin "1") (pinfunction "1_1") (pintype "bidirectional"))
    )
    (net (code "52") (name "unconnected-(IC1-Pad4)") (class "Default")
      (node (ref "IC1") (pin "4") (pinfunction "4_4") (pintype "passive"))
    )
    (net (code "53") (name "unconnected-(IC1-Pad8)") (class "Default")
      (node (ref "IC1") (pin "8") (pinfunction "8_8") (pintype "passive"))
    )
    (net (code "54") (name "unconnected-(IC1-Pad14)") (class "Default")
      (node (ref "IC1") (pin "14") (pinfunction "14_14") (pintype "passive"))
    )
    (net (code "55") (name "unconnected-(IC2-Pad4)") (class "Default")
      (node (ref "IC2") (pin "4") (pinfunction "4_4") (pintype "passive"))
    )
    (net (code "56") (name "unconnected-(IC2-Pad8)") (class "Default")
      (node (ref "IC2") (pin "8") (pinfunction "8_8") (pintype "passive"))
    )
    (net (code "57") (name "unconnected-(IC2-Pad14)") (class "Default")
      (node (ref "IC2") (pin "14") (pinfunction "14_14") (pintype "passive"))
    )
    (net (code "58") (name "unconnected-(IC3-Pad4)") (class "Default")
      (node (ref "IC3") (pin "4") (pinfunction "4_4") (pintype "passive"))
    )
    (net (code "59") (name "unconnected-(IC3-Pad8)") (class "Default")
      (node (ref "IC3") (pin "8") (pinfunction "8_8") (pintype "passive"))
    )
    (net (code "60") (name "unconnected-(IC3-Pad14)") (class "Default")
      (node (ref "IC3") (pin "14") (pinfunction "14_14") (pintype "passive"))
    )
    (net (code "61") (name "unconnected-(IC6-PB0(ICP)-Pad14)") (class "Default")
      (node (ref "IC6") (pin "14") (pinfunction "PB0(ICP)_14") (pintype "bidirectional"))
    )
    (net (code "62") (name "unconnected-(IC6-PB6(XTAL1{slash}TOSC1)-Pad9)") (class "Default")
      (node (ref "IC6") (pin "9") (pinfunction "PB6(XTAL1/TOSC1)_9") (pintype "bidirectional"))
    )
    (net (code "63") (name "unconnected-(IC6-PB7(XTAL2{slash}TOSC2)-Pad10)") (class "Default")
      (node (ref "IC6") (pin "10") (pinfunction "PB7(XTAL2/TOSC2)_10") (pintype "bidirectional"))
    )
    (net (code "64") (name "unconnected-(IC6-PC1(ADC1)-Pad24)") (class "Default")
      (node (ref "IC6") (pin "24") (pinfunction "PC1(ADC1)_24") (pintype "bidirectional"))
    )
    (net (code "65") (name "unconnected-(IC6-PC2(ADC2)-Pad25)") (class "Default")
      (node (ref "IC6") (pin "25") (pinfunction "PC2(ADC2)_25") (pintype "bidirectional"))
    )
    (net (code "66") (name "unconnected-(IC6-PC3(ADC3)-Pad26)") (class "Default")
      (node (ref "IC6") (pin "26") (pinfunction "PC3(ADC3)_26") (pintype "bidirectional"))
    )
    (net (code "67") (name "unconnected-(IC6-PC4(ADC4{slash}SDA)-Pad27)") (class "Default")
      (node (ref "IC6") (pin "27") (pinfunction "PC4(ADC4/SDA)_27") (pintype "bidirectional"))
    )
    (net (code "68") (name "unconnected-(IC6-PC5(ADC5{slash}SCL)-Pad28)") (class "Default")
      (node (ref "IC6") (pin "28") (pinfunction "PC5(ADC5/SCL)_28") (pintype "bidirectional"))
    )
    (net (code "69") (name "unconnected-(IC6-PD3(INT1)-Pad5)") (class "Default")
      (node (ref "IC6") (pin "5") (pinfunction "PD3(INT1)_5") (pintype "bidirectional"))
    )
    (net (code "70") (name "unconnected-(IC6-PD4(XCK{slash}T0)-Pad6)") (class "Default")
      (node (ref "IC6") (pin "6") (pinfunction "PD4(XCK/T0)_6") (pintype "bidirectional"))
    )
    (net (code "71") (name "unconnected-(K1-PadO)") (class "Default")
      (node (ref "K1") (pin "O") (pinfunction "O_O") (pintype "passive"))
    )
    (net (code "72") (name "unconnected-(SV1-Pad3)") (class "Default")
      (node (ref "SV1") (pin "3") (pinfunction "3_3") (pintype "passive"))
    )
    (net (code "73") (name "unconnected-(SV1-Pad5)") (class "Default")
      (node (ref "SV1") (pin "5") (pinfunction "5_5") (pintype "passive"))
    )
    (net (code "74") (name "unconnected-(SV1-Pad7)") (class "Default")
      (node (ref "SV1") (pin "7") (pinfunction "7_7") (pintype "passive"))
    )
    (net (code "75") (name "unconnected-(SV1-Pad8)") (class "Default")
      (node (ref "SV1") (pin "8") (pinfunction "8_8") (pintype "passive"))
    )
    (net (code "76") (name "unconnected-(X7D-SK-Pad4)") (class "Default")
      (node (ref "X7") (pin "4") (pinfunction "SK_4") (pintype "passive"))
    )
  )
)
